# Fuente_de_-_15V.net
KiCad netlist of a schematic drawn in EAGLE
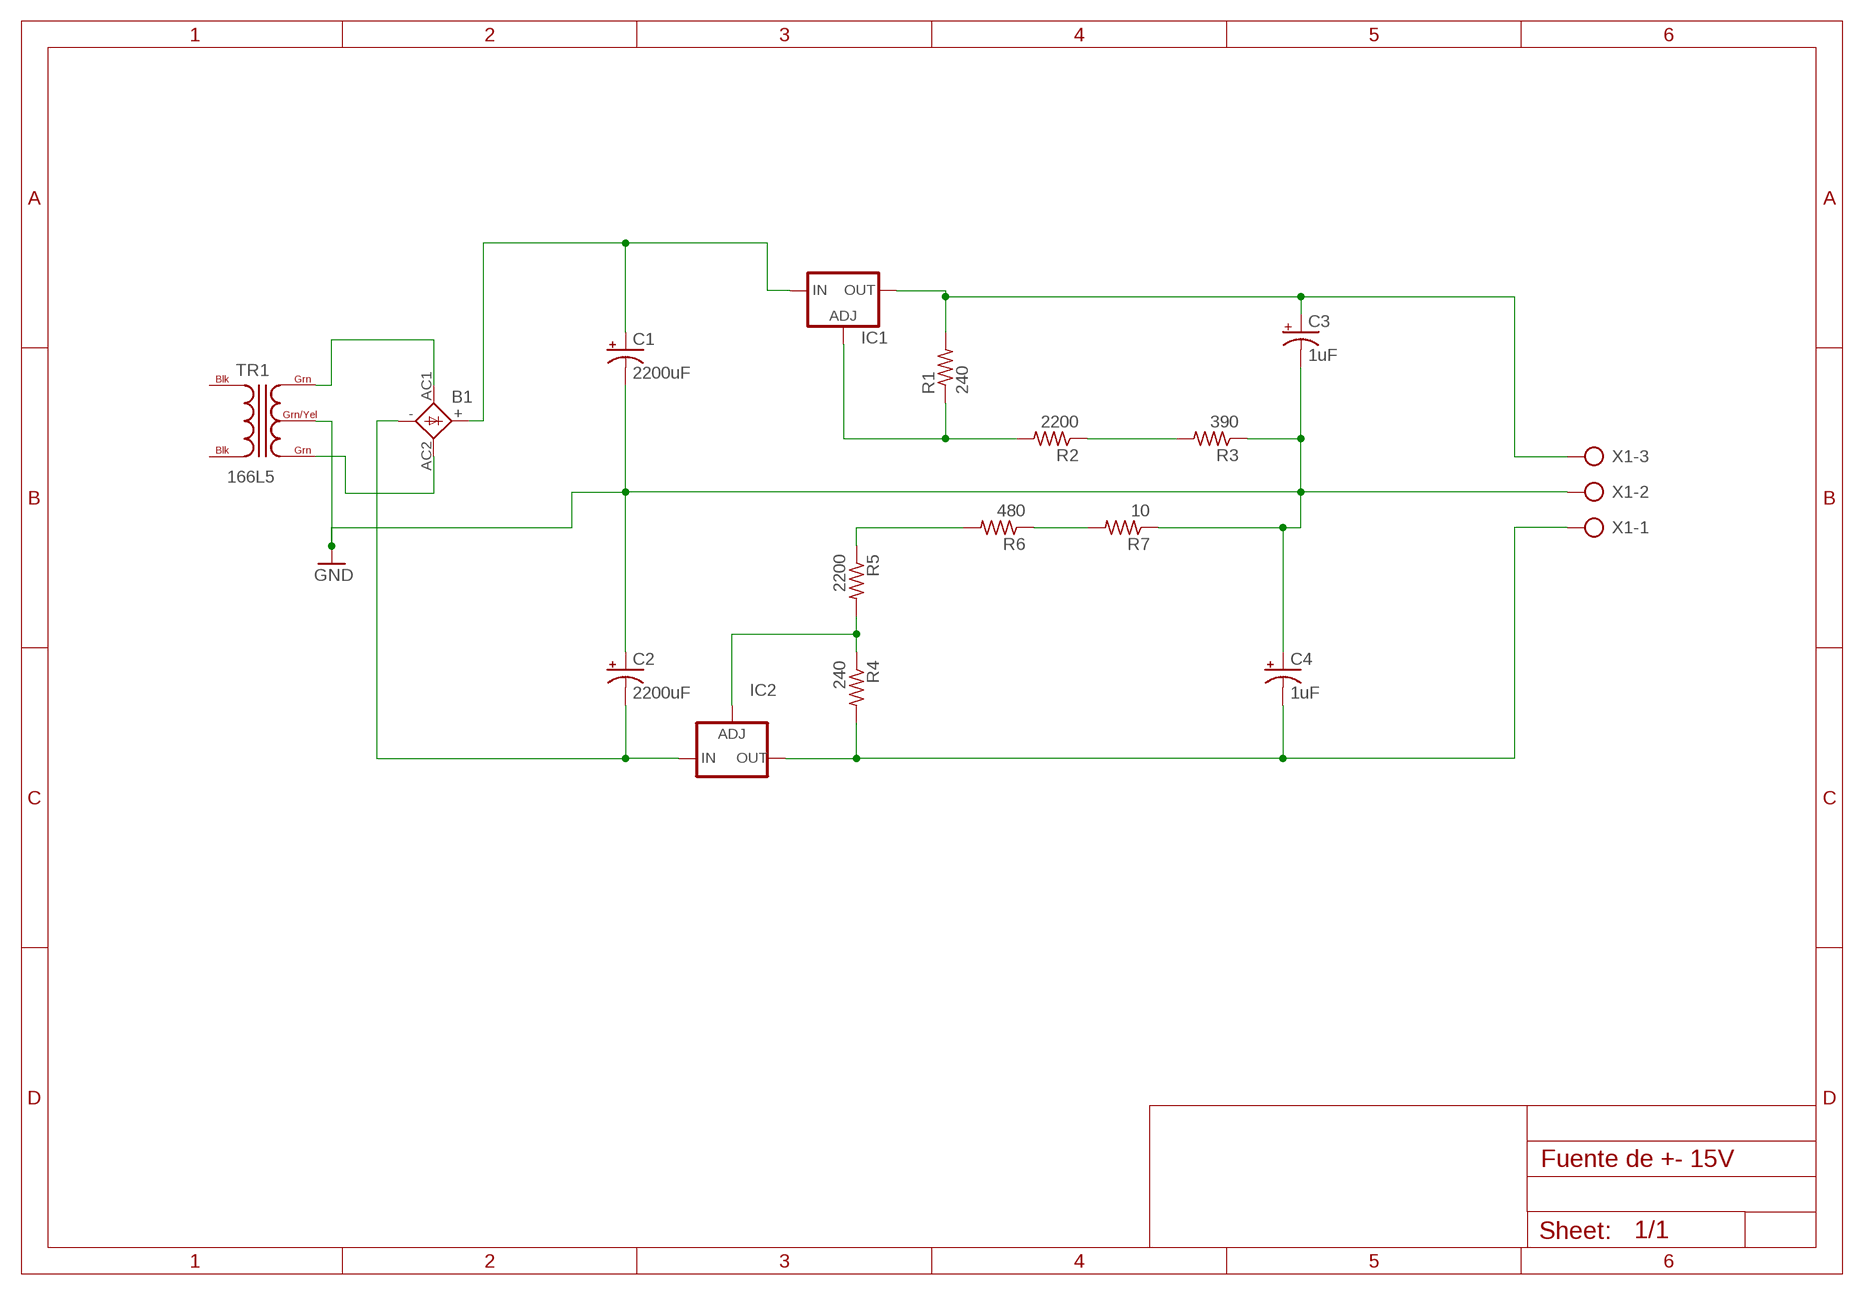
[diagram p0: schematic, sheet 1]

(export (version "E")
  (design (tool "Eeschema 10.0.6"))
  (components
    (comp (ref "B1")
      (value "2KBP")
      (footprint "eagle-import:2KBP")
      (libsource (lib "eagle-import") (part "2KBP"))
    )
    (comp (ref "C1")
      (value "2200uF")
      (footprint "eagle-import:E7,5-16")
      (libsource (lib "eagle-import") (part "CPOL-USE7.5-16"))
    )
    (comp (ref "C2")
      (value "2200uF")
      (footprint "eagle-import:E7,5-16")
      (libsource (lib "eagle-import") (part "CPOL-USE7.5-16"))
    )
    (comp (ref "C3")
      (value "1uF")
      (footprint "eagle-import:E1,8-4")
      (libsource (lib "eagle-import") (part "CPOL-USE1.8-4"))
    )
    (comp (ref "C4")
      (value "1uF")
      (footprint "eagle-import:E1,8-4")
      (libsource (lib "eagle-import") (part "CPOL-USE1.8-4"))
    )
    (comp (ref "IC1")
      (value "LM317TS")
      (footprint "eagle-import:317TS")
      (libsource (lib "eagle-import") (part "LM317TS"))
    )
    (comp (ref "IC2")
      (value "LM337TS")
      (footprint "eagle-import:337TS")
      (libsource (lib "eagle-import") (part "LM337TS"))
    )
    (comp (ref "R1")
      (value "240")
      (footprint "eagle-import:0204_7")
      (libsource (lib "eagle-import") (part "R-US_0204/7"))
    )
    (comp (ref "R2")
      (value "2200")
      (footprint "eagle-import:0204_7")
      (libsource (lib "eagle-import") (part "R-US_0204/7"))
    )
    (comp (ref "R3")
      (value "390")
      (footprint "eagle-import:0204_7")
      (libsource (lib "eagle-import") (part "R-US_0204/7"))
    )
    (comp (ref "R4")
      (value "240")
      (footprint "eagle-import:0204_7")
      (libsource (lib "eagle-import") (part "R-US_0204/7"))
    )
    (comp (ref "R5")
      (value "2200")
      (footprint "eagle-import:0204_7")
      (libsource (lib "eagle-import") (part "R-US_0204/7"))
    )
    (comp (ref "R6")
      (value "480")
      (footprint "eagle-import:0204_7")
      (libsource (lib "eagle-import") (part "R-US_0204/7"))
    )
    (comp (ref "R7")
      (value "10")
      (footprint "eagle-import:0204_7")
      (libsource (lib "eagle-import") (part "R-US_0204/7"))
    )
    (comp (ref "TR1")
      (value "166L5")
      (footprint "eagle-import:C7H")
      (libsource (lib "eagle-import") (part "166L5"))
    )
    (comp (ref "X1")
      (value "AK300/3")
      (footprint "eagle-import:AK300_3")
      (libsource (lib "eagle-import") (part "AK300/3"))
    )
  )
  (nets
    (net (code "1") (name "GND") (class "Default")
      (node (ref "C1") (pin "-") (pinfunction "-_-") (pintype "passive"))
      (node (ref "C2") (pin "+") (pinfunction "+_+") (pintype "passive"))
      (node (ref "C3") (pin "-") (pinfunction "-_-") (pintype "passive"))
      (node (ref "C4") (pin "+") (pinfunction "+_+") (pintype "passive"))
      (node (ref "R3") (pin "1") (pinfunction "1_1") (pintype "passive"))
      (node (ref "R7") (pin "1") (pinfunction "1_1") (pintype "passive"))
      (node (ref "TR1") (pin "GRN/YEL") (pinfunction "GRN/YEL_GRN/YEL") (pintype "passive"))
      (node (ref "X1") (pin "2") (pinfunction "KL_2") (pintype "passive"))
    )
    (net (code "2") (name "Net-(B1-PadAC1)") (class "Default")
      (node (ref "B1") (pin "AC1") (pinfunction "AC1_AC1") (pintype "passive"))
      (node (ref "TR1") (pin "GRN@1") (pinfunction "GRN_GRN@1") (pintype "passive"))
    )
    (net (code "3") (name "Net-(B1-PadAC2)") (class "Default")
      (node (ref "B1") (pin "AC2") (pinfunction "AC2_AC2") (pintype "passive"))
      (node (ref "TR1") (pin "GRN@2") (pinfunction "GRN_GRN@2") (pintype "passive"))
    )
    (net (code "4") (name "Net-(IC1-ADJ)") (class "Default")
      (node (ref "IC1") (pin "1") (pinfunction "ADJ_1") (pintype "input"))
      (node (ref "R1") (pin "1") (pinfunction "1_1") (pintype "passive"))
      (node (ref "R2") (pin "2") (pinfunction "2_2") (pintype "passive"))
    )
    (net (code "5") (name "Net-(IC1-IN)") (class "Default")
      (node (ref "B1") (pin "+") (pinfunction "+_+") (pintype "passive"))
      (node (ref "C1") (pin "+") (pinfunction "+_+") (pintype "passive"))
      (node (ref "IC1") (pin "3") (pinfunction "IN_3") (pintype "input"))
    )
    (net (code "6") (name "Net-(IC1-OUT)") (class "Default")
      (node (ref "C3") (pin "+") (pinfunction "+_+") (pintype "passive"))
      (node (ref "IC1") (pin "2") (pinfunction "OUT_2") (pintype "passive"))
      (node (ref "R1") (pin "2") (pinfunction "2_2") (pintype "passive"))
      (node (ref "X1") (pin "3") (pinfunction "KL_3") (pintype "passive"))
    )
    (net (code "7") (name "Net-(IC2-ADJ)") (class "Default")
      (node (ref "IC2") (pin "1") (pinfunction "ADJ_1") (pintype "input"))
      (node (ref "R4") (pin "1") (pinfunction "1_1") (pintype "passive"))
      (node (ref "R5") (pin "2") (pinfunction "2_2") (pintype "passive"))
    )
    (net (code "8") (name "Net-(IC2-IN)") (class "Default")
      (node (ref "B1") (pin "-") (pinfunction "-_-") (pintype "passive"))
      (node (ref "C2") (pin "-") (pinfunction "-_-") (pintype "passive"))
      (node (ref "IC2") (pin "2") (pinfunction "IN_2") (pintype "input"))
    )
    (net (code "9") (name "Net-(IC2-OUT)") (class "Default")
      (node (ref "C4") (pin "-") (pinfunction "-_-") (pintype "passive"))
      (node (ref "IC2") (pin "3") (pinfunction "OUT_3") (pintype "passive"))
      (node (ref "R4") (pin "2") (pinfunction "2_2") (pintype "passive"))
      (node (ref "X1") (pin "1") (pinfunction "KL_1") (pintype "passive"))
    )
    (net (code "10") (name "Net-(R2-Pad1)") (class "Default")
      (node (ref "R2") (pin "1") (pinfunction "1_1") (pintype "passive"))
      (node (ref "R3") (pin "2") (pinfunction "2_2") (pintype "passive"))
    )
    (net (code "11") (name "Net-(R5-Pad1)") (class "Default")
      (node (ref "R5") (pin "1") (pinfunction "1_1") (pintype "passive"))
      (node (ref "R6") (pin "2") (pinfunction "2_2") (pintype "passive"))
    )
    (net (code "12") (name "Net-(R6-Pad1)") (class "Default")
      (node (ref "R6") (pin "1") (pinfunction "1_1") (pintype "passive"))
      (node (ref "R7") (pin "2") (pinfunction "2_2") (pintype "passive"))
    )
    (net (code "13") (name "unconnected-(TR1-BLK-PadBLK@1)") (class "Default")
      (node (ref "TR1") (pin "BLK@1") (pinfunction "BLK_BLK@1") (pintype "passive"))
    )
    (net (code "14") (name "unconnected-(TR1-BLK-PadBLK@2)") (class "Default")
      (node (ref "TR1") (pin "BLK@2") (pinfunction "BLK_BLK@2") (pintype "passive"))
    )
  )
)
